# M246A.net
KiCad netlist of a schematic drawn in EAGLE
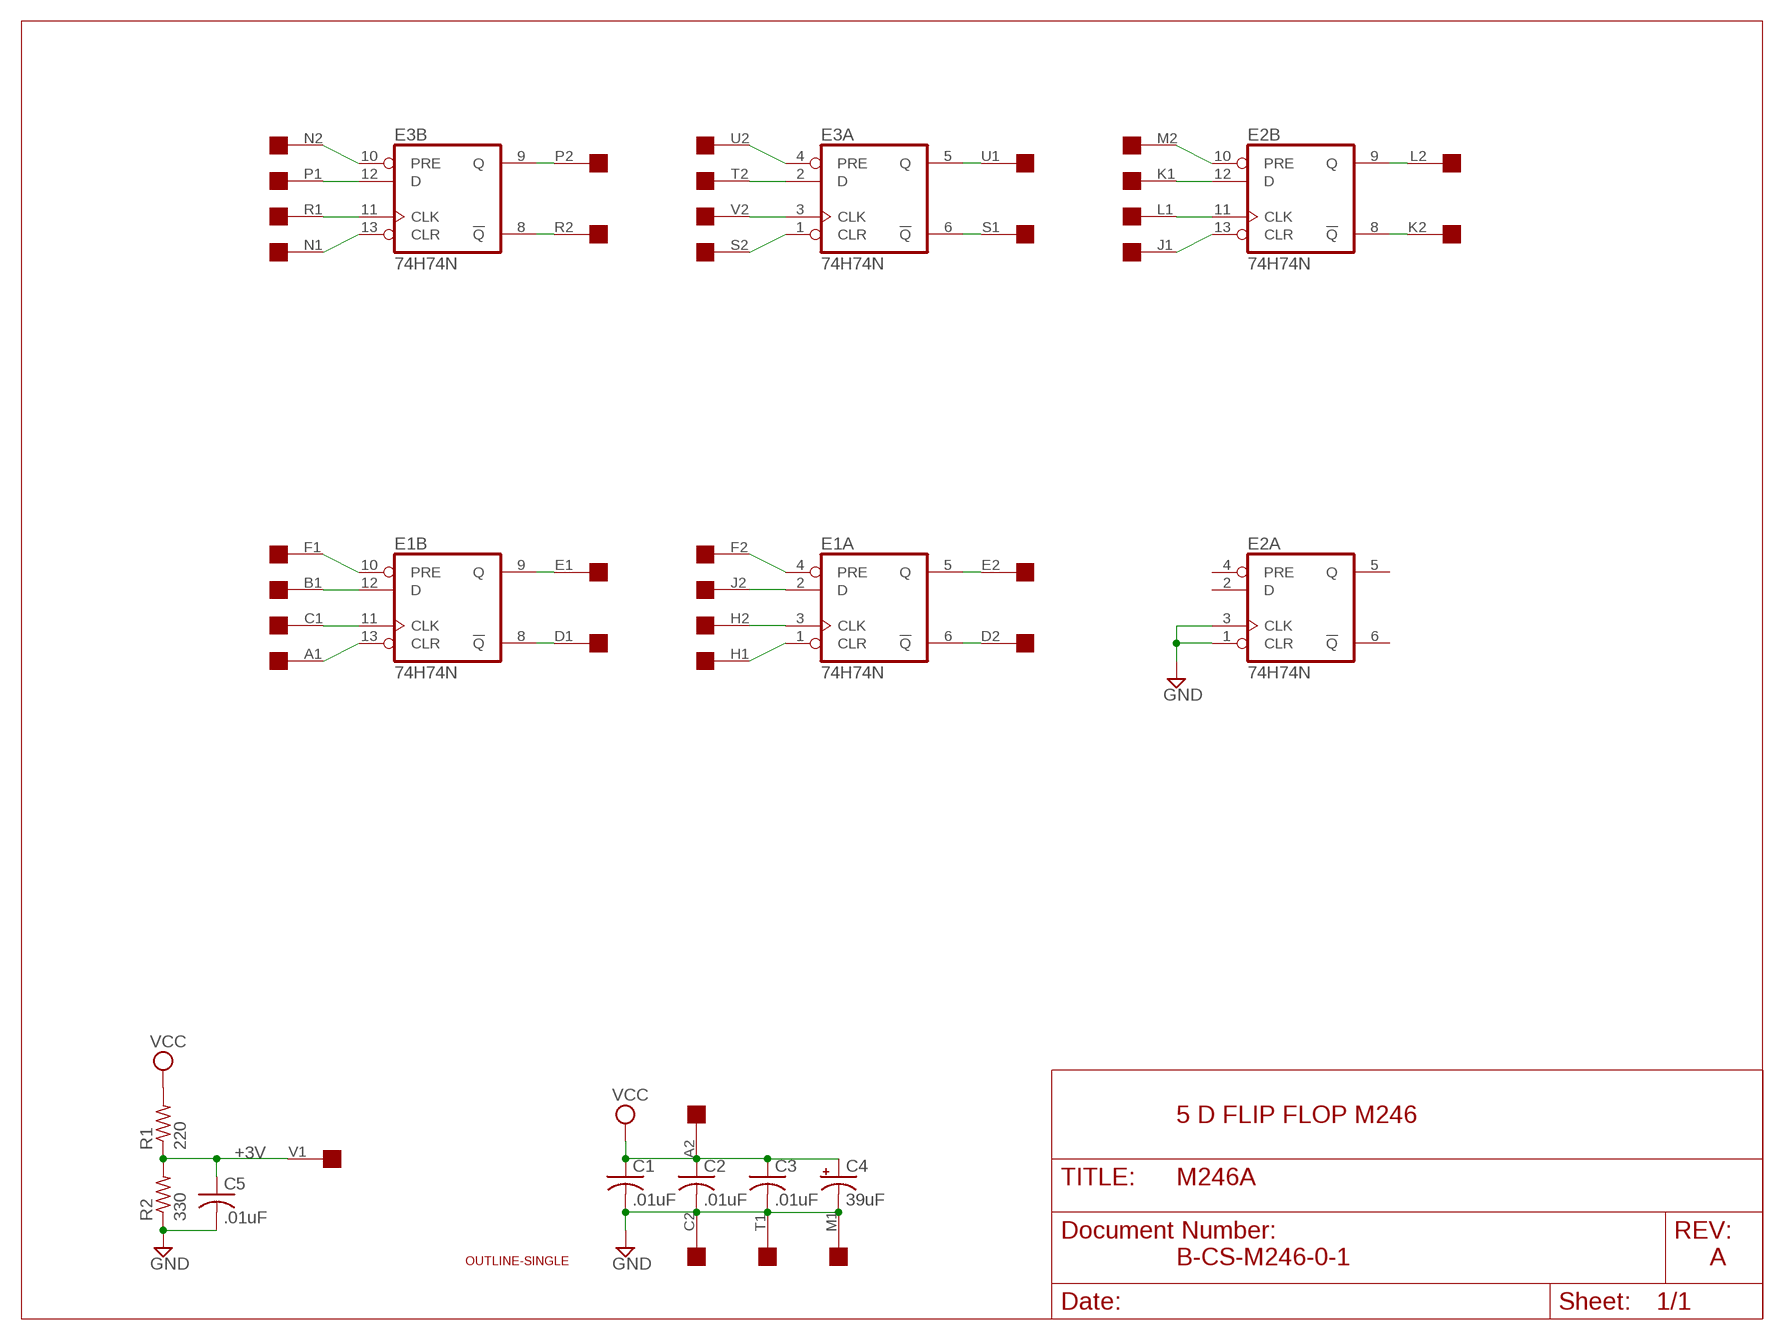
[diagram p0: schematic, sheet 1]

(export (version "E")
  (design (tool "Eeschema 10.0.6"))
  (components
    (comp (ref "C1")
      (value ".01uF")
      (footprint "eagle-import:C050-025X075")
      (libsource (lib "eagle-import") (part "C-US050-025X075"))
    )
    (comp (ref "C2")
      (value ".01uF")
      (footprint "eagle-import:C050-025X075")
      (libsource (lib "eagle-import") (part "C-US050-025X075"))
    )
    (comp (ref "C3")
      (value ".01uF")
      (footprint "eagle-import:C050-025X075")
      (libsource (lib "eagle-import") (part "C-US050-025X075"))
    )
    (comp (ref "C4")
      (value "39uF")
      (footprint "eagle-import:E12-8")
      (libsource (lib "eagle-import") (part "CPOL-USE20-8AXIAL"))
    )
    (comp (ref "C5")
      (value ".01uF")
      (footprint "eagle-import:C050-025X075")
      (libsource (lib "eagle-import") (part "C-US050-025X075"))
    )
    (comp (ref "E1")
      (value "74H74N")
      (footprint "eagle-import:DIL14")
      (libsource (lib "eagle-import") (part "7474NS"))
    )
    (comp (ref "E2")
      (value "74H74N")
      (footprint "eagle-import:DIL14")
      (libsource (lib "eagle-import") (part "7474NS"))
    )
    (comp (ref "E3")
      (value "74H74N")
      (footprint "eagle-import:DIL14")
      (libsource (lib "eagle-import") (part "7474NS"))
    )
    (comp (ref "R1")
      (value "220")
      (footprint "eagle-import:0207_10")
      (libsource (lib "eagle-import") (part "R-US_0207/10"))
    )
    (comp (ref "R2")
      (value "330")
      (footprint "eagle-import:0207_10")
      (libsource (lib "eagle-import") (part "R-US_0207/10"))
    )
    (comp (ref "U$1")
      (value "OUTLINE-SINGLE")
      (footprint "eagle-import:SINGLE")
      (libsource (lib "eagle-import") (part "OUTLINE-SINGLE"))
    )
    (comp (ref "U$2")
      (value "EDGE-2CONNECTOR")
      (footprint "eagle-import:EDGE-CON2")
      (libsource (lib "eagle-import") (part "EDGE-2CONNECTOR"))
    )
  )
  (nets
    (net (code "1") (name "/+3V") (class "Default")
      (node (ref "C5") (pin "1") (pinfunction "1_1") (pintype "passive"))
      (node (ref "R1") (pin "1") (pinfunction "1_1") (pintype "passive"))
      (node (ref "R2") (pin "2") (pinfunction "2_2") (pintype "passive"))
      (node (ref "U$2") (pin "V1") (pinfunction "1_V1") (pintype "bidirectional"))
    )
    (net (code "2") (name "GND") (class "Default")
      (node (ref "C1") (pin "2") (pinfunction "2_2") (pintype "passive"))
      (node (ref "C2") (pin "2") (pinfunction "2_2") (pintype "passive"))
      (node (ref "C3") (pin "2") (pinfunction "2_2") (pintype "passive"))
      (node (ref "C4") (pin "-") (pinfunction "-_-") (pintype "passive"))
      (node (ref "C5") (pin "2") (pinfunction "2_2") (pintype "passive"))
      (node (ref "E2") (pin "1") (pinfunction "CLR_1") (pintype "input"))
      (node (ref "E2") (pin "3") (pinfunction "CLK_3") (pintype "input"))
      (node (ref "R2") (pin "1") (pinfunction "1_1") (pintype "passive"))
      (node (ref "U$2") (pin "C2") (pinfunction "1_C2") (pintype "bidirectional"))
      (node (ref "U$2") (pin "M1") (pinfunction "1_M1") (pintype "bidirectional"))
      (node (ref "U$2") (pin "T1") (pinfunction "1_T1") (pintype "bidirectional"))
    )
    (net (code "3") (name "Net-(E1A-CLK)") (class "Default")
      (node (ref "E1") (pin "3") (pinfunction "CLK_3") (pintype "input"))
      (node (ref "U$2") (pin "H2") (pinfunction "1_H2") (pintype "bidirectional"))
    )
    (net (code "4") (name "Net-(E1A-CLR)") (class "Default")
      (node (ref "E1") (pin "1") (pinfunction "CLR_1") (pintype "input"))
      (node (ref "U$2") (pin "H1") (pinfunction "1_H1") (pintype "bidirectional"))
    )
    (net (code "5") (name "Net-(E1A-D)") (class "Default")
      (node (ref "E1") (pin "2") (pinfunction "D_2") (pintype "input"))
      (node (ref "U$2") (pin "J2") (pinfunction "1_J2") (pintype "bidirectional"))
    )
    (net (code "6") (name "Net-(E1A-PRE)") (class "Default")
      (node (ref "E1") (pin "4") (pinfunction "PRE_4") (pintype "input"))
      (node (ref "U$2") (pin "F2") (pinfunction "1_F2") (pintype "bidirectional"))
    )
    (net (code "7") (name "Net-(E1A-Q)") (class "Default")
      (node (ref "E1") (pin "5") (pinfunction "Q_5") (pintype "output"))
      (node (ref "U$2") (pin "E2") (pinfunction "1_E2") (pintype "bidirectional"))
    )
    (net (code "8") (name "Net-(E1A-~{Q})") (class "Default")
      (node (ref "E1") (pin "6") (pinfunction "~{Q}_6") (pintype "output"))
      (node (ref "U$2") (pin "D2") (pinfunction "1_D2") (pintype "bidirectional"))
    )
    (net (code "9") (name "Net-(E1B-CLK)") (class "Default")
      (node (ref "E1") (pin "11") (pinfunction "CLK_11") (pintype "input"))
      (node (ref "U$2") (pin "C1") (pinfunction "1_C1") (pintype "bidirectional"))
    )
    (net (code "10") (name "Net-(E1B-CLR)") (class "Default")
      (node (ref "E1") (pin "13") (pinfunction "CLR_13") (pintype "input"))
      (node (ref "U$2") (pin "A1") (pinfunction "1_A1") (pintype "bidirectional"))
    )
    (net (code "11") (name "Net-(E1B-D)") (class "Default")
      (node (ref "E1") (pin "12") (pinfunction "D_12") (pintype "input"))
      (node (ref "U$2") (pin "B1") (pinfunction "1_B1") (pintype "bidirectional"))
    )
    (net (code "12") (name "Net-(E1B-PRE)") (class "Default")
      (node (ref "E1") (pin "10") (pinfunction "PRE_10") (pintype "input"))
      (node (ref "U$2") (pin "F1") (pinfunction "1_F1") (pintype "bidirectional"))
    )
    (net (code "13") (name "Net-(E1B-Q)") (class "Default")
      (node (ref "E1") (pin "9") (pinfunction "Q_9") (pintype "output"))
      (node (ref "U$2") (pin "E1") (pinfunction "1_E1") (pintype "bidirectional"))
    )
    (net (code "14") (name "Net-(E1B-~{Q})") (class "Default")
      (node (ref "E1") (pin "8") (pinfunction "~{Q}_8") (pintype "output"))
      (node (ref "U$2") (pin "D1") (pinfunction "1_D1") (pintype "bidirectional"))
    )
    (net (code "15") (name "Net-(E2B-CLK)") (class "Default")
      (node (ref "E2") (pin "11") (pinfunction "CLK_11") (pintype "input"))
      (node (ref "U$2") (pin "L1") (pinfunction "1_L1") (pintype "bidirectional"))
    )
    (net (code "16") (name "Net-(E2B-CLR)") (class "Default")
      (node (ref "E2") (pin "13") (pinfunction "CLR_13") (pintype "input"))
      (node (ref "U$2") (pin "J1") (pinfunction "1_J1") (pintype "bidirectional"))
    )
    (net (code "17") (name "Net-(E2B-D)") (class "Default")
      (node (ref "E2") (pin "12") (pinfunction "D_12") (pintype "input"))
      (node (ref "U$2") (pin "K1") (pinfunction "1_K1") (pintype "bidirectional"))
    )
    (net (code "18") (name "Net-(E2B-PRE)") (class "Default")
      (node (ref "E2") (pin "10") (pinfunction "PRE_10") (pintype "input"))
      (node (ref "U$2") (pin "M2") (pinfunction "1_M2") (pintype "bidirectional"))
    )
    (net (code "19") (name "Net-(E2B-Q)") (class "Default")
      (node (ref "E2") (pin "9") (pinfunction "Q_9") (pintype "output"))
      (node (ref "U$2") (pin "L2") (pinfunction "1_L2") (pintype "bidirectional"))
    )
    (net (code "20") (name "Net-(E2B-~{Q})") (class "Default")
      (node (ref "E2") (pin "8") (pinfunction "~{Q}_8") (pintype "output"))
      (node (ref "U$2") (pin "K2") (pinfunction "1_K2") (pintype "bidirectional"))
    )
    (net (code "21") (name "Net-(E3A-CLK)") (class "Default")
      (node (ref "E3") (pin "3") (pinfunction "CLK_3") (pintype "input"))
      (node (ref "U$2") (pin "V2") (pinfunction "1_V2") (pintype "bidirectional"))
    )
    (net (code "22") (name "Net-(E3A-CLR)") (class "Default")
      (node (ref "E3") (pin "1") (pinfunction "CLR_1") (pintype "input"))
      (node (ref "U$2") (pin "S2") (pinfunction "1_S2") (pintype "bidirectional"))
    )
    (net (code "23") (name "Net-(E3A-D)") (class "Default")
      (node (ref "E3") (pin "2") (pinfunction "D_2") (pintype "input"))
      (node (ref "U$2") (pin "T2") (pinfunction "1_T2") (pintype "bidirectional"))
    )
    (net (code "24") (name "Net-(E3A-PRE)") (class "Default")
      (node (ref "E3") (pin "4") (pinfunction "PRE_4") (pintype "input"))
      (node (ref "U$2") (pin "U2") (pinfunction "1_U2") (pintype "bidirectional"))
    )
    (net (code "25") (name "Net-(E3A-Q)") (class "Default")
      (node (ref "E3") (pin "5") (pinfunction "Q_5") (pintype "output"))
      (node (ref "U$2") (pin "U1") (pinfunction "1_U1") (pintype "bidirectional"))
    )
    (net (code "26") (name "Net-(E3A-~{Q})") (class "Default")
      (node (ref "E3") (pin "6") (pinfunction "~{Q}_6") (pintype "output"))
      (node (ref "U$2") (pin "S1") (pinfunction "1_S1") (pintype "bidirectional"))
    )
    (net (code "27") (name "Net-(E3B-CLK)") (class "Default")
      (node (ref "E3") (pin "11") (pinfunction "CLK_11") (pintype "input"))
      (node (ref "U$2") (pin "R1") (pinfunction "1_R1") (pintype "bidirectional"))
    )
    (net (code "28") (name "Net-(E3B-CLR)") (class "Default")
      (node (ref "E3") (pin "13") (pinfunction "CLR_13") (pintype "input"))
      (node (ref "U$2") (pin "N1") (pinfunction "1_N1") (pintype "bidirectional"))
    )
    (net (code "29") (name "Net-(E3B-D)") (class "Default")
      (node (ref "E3") (pin "12") (pinfunction "D_12") (pintype "input"))
      (node (ref "U$2") (pin "P1") (pinfunction "1_P1") (pintype "bidirectional"))
    )
    (net (code "30") (name "Net-(E3B-PRE)") (class "Default")
      (node (ref "E3") (pin "10") (pinfunction "PRE_10") (pintype "input"))
      (node (ref "U$2") (pin "N2") (pinfunction "1_N2") (pintype "bidirectional"))
    )
    (net (code "31") (name "Net-(E3B-Q)") (class "Default")
      (node (ref "E3") (pin "9") (pinfunction "Q_9") (pintype "output"))
      (node (ref "U$2") (pin "P2") (pinfunction "1_P2") (pintype "bidirectional"))
    )
    (net (code "32") (name "Net-(E3B-~{Q})") (class "Default")
      (node (ref "E3") (pin "8") (pinfunction "~{Q}_8") (pintype "output"))
      (node (ref "U$2") (pin "R2") (pinfunction "1_R2") (pintype "bidirectional"))
    )
    (net (code "33") (name "VCC") (class "Default")
      (node (ref "C1") (pin "1") (pinfunction "1_1") (pintype "passive"))
      (node (ref "C2") (pin "1") (pinfunction "1_1") (pintype "passive"))
      (node (ref "C3") (pin "1") (pinfunction "1_1") (pintype "passive"))
      (node (ref "C4") (pin "+") (pinfunction "+_+") (pintype "passive"))
      (node (ref "R1") (pin "2") (pinfunction "2_2") (pintype "passive"))
      (node (ref "U$2") (pin "A2") (pinfunction "1_A2") (pintype "bidirectional"))
    )
    (net (code "34") (name "unconnected-(E2A-D-Pad2)") (class "Default")
      (node (ref "E2") (pin "2") (pinfunction "D_2") (pintype "input"))
    )
    (net (code "35") (name "unconnected-(E2A-PRE-Pad4)") (class "Default")
      (node (ref "E2") (pin "4") (pinfunction "PRE_4") (pintype "input"))
    )
    (net (code "36") (name "unconnected-(E2A-Q-Pad5)") (class "Default")
      (node (ref "E2") (pin "5") (pinfunction "Q_5") (pintype "output"))
    )
    (net (code "37") (name "unconnected-(E2A-~{Q}-Pad6)") (class "Default")
      (node (ref "E2") (pin "6") (pinfunction "~{Q}_6") (pintype "output"))
    )
  )
)
